# 410_H_BRIDGE_CORE.net
KiCad netlist of a schematic drawn in Altium Designer
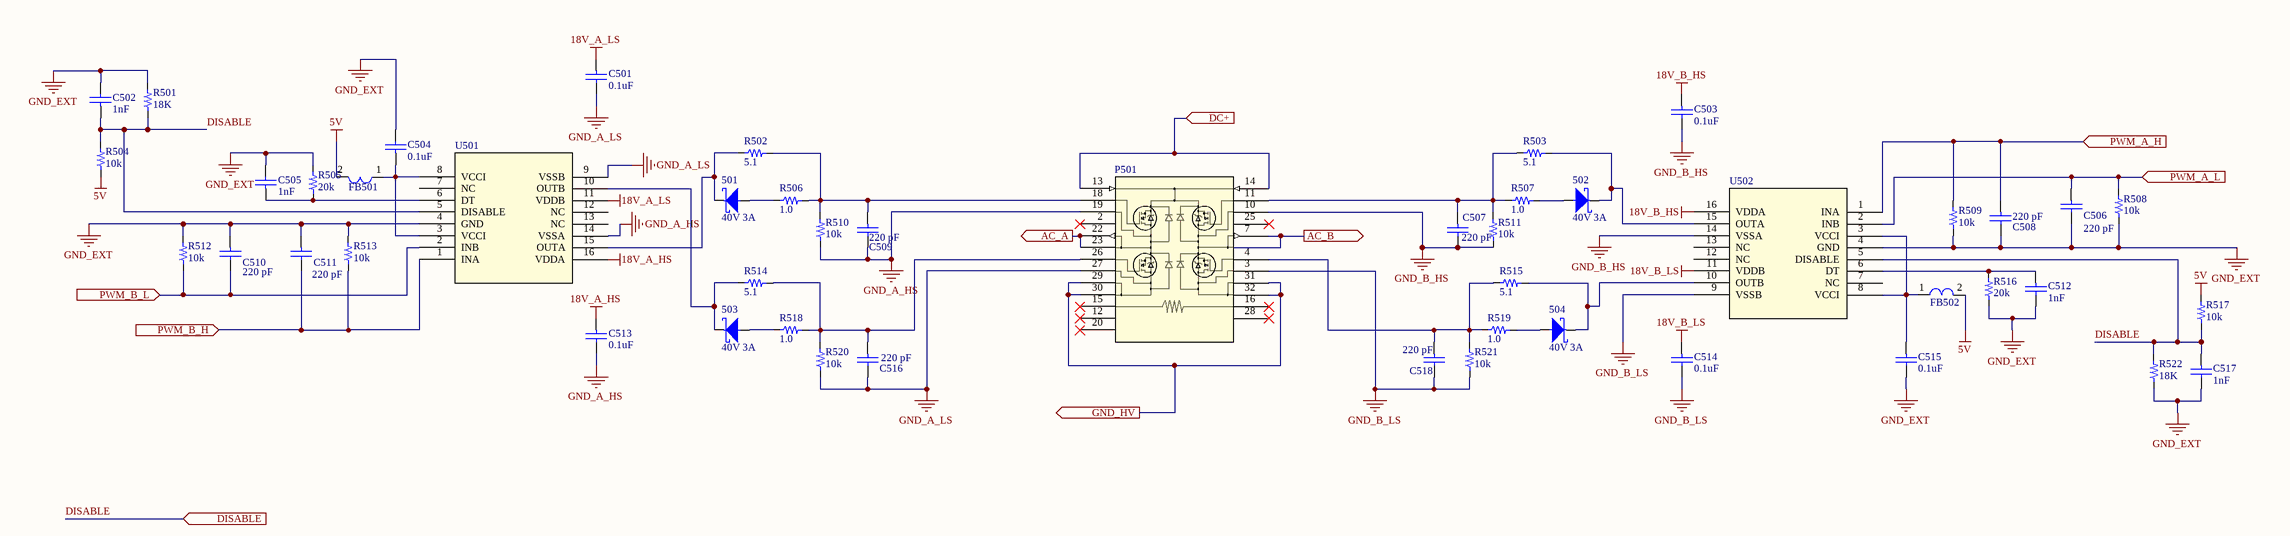
[diagram p0: 410_H_BRIDGE_CORE.SchDoc]

(export (version "E")
  (design (tool "Eeschema 10.0.6"))
  (components
    (comp (ref "501")
      (value "40V 3A")
      (footprint "SMA")
      (description "40V Independent 3A 550mV@3A SMA Schottky Diodes ROHS")
      (fields (field (name "MANUFACTURER") "TDSEMIC") (field (name "MANUFACTURER PART NUMBER") "SS34-TD"))
      (libsource (lib "shared_lib_1") (part "D_Schottky_40V_3A_SMA"))
    )
    (comp (ref "502")
      (value "40V 3A")
      (footprint "SMA")
      (description "40V Independent 3A 550mV@3A SMA Schottky Diodes ROHS")
      (fields (field (name "MANUFACTURER") "TDSEMIC") (field (name "MANUFACTURER PART NUMBER") "SS34-TD"))
      (libsource (lib "shared_lib_1") (part "D_Schottky_40V_3A_SMA"))
    )
    (comp (ref "503")
      (value "40V 3A")
      (footprint "SMA")
      (description "40V Independent 3A 550mV@3A SMA Schottky Diodes ROHS")
      (fields (field (name "MANUFACTURER") "TDSEMIC") (field (name "MANUFACTURER PART NUMBER") "SS34-TD"))
      (libsource (lib "shared_lib_1") (part "D_Schottky_40V_3A_SMA"))
    )
    (comp (ref "504")
      (value "40V 3A")
      (footprint "SMA")
      (description "40V Independent 3A 550mV@3A SMA Schottky Diodes ROHS")
      (fields (field (name "MANUFACTURER") "TDSEMIC") (field (name "MANUFACTURER PART NUMBER") "SS34-TD"))
      (libsource (lib "shared_lib_1") (part "D_Schottky_40V_3A_SMA"))
    )
    (comp (ref "C501")
      (value "0.1uF")
      (footprint "0603_cap")
      (description "50V 100nF Y5V -20%~+80% 0603 Multilayer Ceramic Capacitors MLCC - SMD/SMT ROHS")
      (fields
        (field (name "MANUFACTURER") "Walsin Tech Corp")
        (field (name "MANUFACTURER PART NUMBER") "0603F104Z500CT")
      )
      (libsource (lib "shared_lib_1") (part "Cap_0.1uF_0603_50V"))
    )
    (comp (ref "C502")
      (value "1nF")
      (footprint "0603_cap")
      (description "50V 1nF X7R ±10% 0603 Multilayer Ceramic Capacitors MLCC - SMD/SMT ROHS")
      (fields
        (field (name "MANUFACTURER") "YAGEO")
        (field (name "MANUFACTURER PART NUMBER") "CC0603KRX7R9BB102")
      )
      (libsource (lib "shared_lib_1") (part "Cap_1nF_0603_50V"))
    )
    (comp (ref "C503")
      (value "0.1uF")
      (footprint "0603_cap")
      (description "CAP CER 100nF 50V Y5V 0603")
      (fields
        (field (name "MANUFACTURER") "FOJAN")
        (field (name "MANUFACTURER PART NUMBER") "FCC0603F104Z500CT")
      )
      (libsource (lib "shared_lib_1") (part "Cap_0.1uF_0603_50V"))
    )
    (comp (ref "C504")
      (value "0.1uF")
      (footprint "0603_cap")
      (description "50V 100nF Y5V -20%~+80% 0603 Multilayer Ceramic Capacitors MLCC - SMD/SMT ROHS")
      (fields
        (field (name "MANUFACTURER") "Walsin Tech Corp")
        (field (name "MANUFACTURER PART NUMBER") "0603F104Z500CT")
      )
      (libsource (lib "shared_lib_1") (part "Cap_0.1uF_0603_50V"))
    )
    (comp (ref "C505")
      (value "1nF")
      (footprint "0603_cap")
      (description "50V 1nF X7R ±10% 0603 Multilayer Ceramic Capacitors MLCC - SMD/SMT ROHS")
      (fields
        (field (name "MANUFACTURER") "YAGEO")
        (field (name "MANUFACTURER PART NUMBER") "CC0603KRX7R9BB102")
      )
      (libsource (lib "shared_lib_1") (part "Cap_1nF_0603_50V"))
    )
    (comp (ref "C506")
      (value "220 pF")
      (footprint "0603_cap")
      (description "CAP CER 220pF 50V X7R 0603")
      (fields
        (field (name "MANUFACTURER") "Samsung Electro-Mechanics")
        (field (name "MANUFACTURER PART NUMBER") "CL10B221KB8NNNC")
      )
      (libsource (lib "shared_lib_1") (part "CAP CER_220PF_50V_X7R_0603"))
    )
    (comp (ref "C507")
      (value "220 pF")
      (footprint "0603_cap")
      (description "CAP CER 220pF 50V X7R 0603")
      (fields
        (field (name "MANUFACTURER") "Samsung Electro-Mechanics")
        (field (name "MANUFACTURER PART NUMBER") "CL10B221KB8NNNC")
      )
      (libsource (lib "shared_lib_1") (part "CAP CER_220PF_50V_X7R_0603"))
    )
    (comp (ref "C508")
      (value "220 pF")
      (footprint "0603_cap")
      (description "CAP CER 220pF 50V X7R 0603")
      (fields
        (field (name "MANUFACTURER") "Samsung Electro-Mechanics")
        (field (name "MANUFACTURER PART NUMBER") "CL10B221KB8NNNC")
      )
      (libsource (lib "shared_lib_1") (part "CAP CER_220PF_50V_X7R_0603"))
    )
    (comp (ref "C509")
      (value "220 pF")
      (footprint "0603_cap")
      (description "CAP CER 220pF 50V X7R 0603")
      (fields
        (field (name "MANUFACTURER") "Samsung Electro-Mechanics")
        (field (name "MANUFACTURER PART NUMBER") "CL10B221KB8NNNC")
      )
      (libsource (lib "shared_lib_1") (part "CAP CER_220PF_50V_X7R_0603"))
    )
    (comp (ref "C510")
      (value "220 pF")
      (footprint "0603_cap")
      (description "CAP CER 220pF 50V X7R 0603")
      (fields
        (field (name "MANUFACTURER") "Samsung Electro-Mechanics")
        (field (name "MANUFACTURER PART NUMBER") "CL10B221KB8NNNC")
      )
      (libsource (lib "shared_lib_1") (part "CAP CER_220PF_50V_X7R_0603"))
    )
    (comp (ref "C511")
      (value "220 pF")
      (footprint "0603_cap")
      (description "CAP CER 220pF 50V X7R 0603")
      (fields
        (field (name "MANUFACTURER") "Samsung Electro-Mechanics")
        (field (name "MANUFACTURER PART NUMBER") "CL10B221KB8NNNC")
      )
      (libsource (lib "shared_lib_1") (part "CAP CER_220PF_50V_X7R_0603"))
    )
    (comp (ref "C512")
      (value "1nF")
      (footprint "0603_cap")
      (description "50V 1nF X7R ±10% 0603 Multilayer Ceramic Capacitors MLCC - SMD/SMT ROHS")
      (fields
        (field (name "MANUFACTURER") "YAGEO")
        (field (name "MANUFACTURER PART NUMBER") "CC0603KRX7R9BB102")
      )
      (libsource (lib "shared_lib_1") (part "Cap_1nF_0603_50V"))
    )
    (comp (ref "C513")
      (value "0.1uF")
      (footprint "0603_cap")
      (description "50V 100nF Y5V -20%~+80% 0603 Multilayer Ceramic Capacitors MLCC - SMD/SMT ROHS")
      (fields
        (field (name "MANUFACTURER") "Walsin Tech Corp")
        (field (name "MANUFACTURER PART NUMBER") "0603F104Z500CT")
      )
      (libsource (lib "shared_lib_1") (part "Cap_0.1uF_0603_50V"))
    )
    (comp (ref "C514")
      (value "0.1uF")
      (footprint "0603_cap")
      (description "50V 100nF Y5V -20%~+80% 0603 Multilayer Ceramic Capacitors MLCC - SMD/SMT ROHS")
      (fields
        (field (name "MANUFACTURER") "Walsin Tech Corp")
        (field (name "MANUFACTURER PART NUMBER") "0603F104Z500CT")
      )
      (libsource (lib "shared_lib_1") (part "Cap_0.1uF_0603_50V"))
    )
    (comp (ref "C515")
      (value "0.1uF")
      (footprint "0603_cap")
      (description "50V 100nF Y5V -20%~+80% 0603 Multilayer Ceramic Capacitors MLCC - SMD/SMT ROHS")
      (fields
        (field (name "MANUFACTURER") "Walsin Tech Corp")
        (field (name "MANUFACTURER PART NUMBER") "0603F104Z500CT")
      )
      (libsource (lib "shared_lib_1") (part "Cap_0.1uF_0603_50V"))
    )
    (comp (ref "C516")
      (value "220 pF")
      (footprint "0603_cap")
      (description "CAP CER 220pF 50V X7R 0603")
      (fields
        (field (name "MANUFACTURER") "Samsung Electro-Mechanics")
        (field (name "MANUFACTURER PART NUMBER") "CL10B221KB8NNNC")
      )
      (libsource (lib "shared_lib_1") (part "CAP CER_220PF_50V_X7R_0603"))
    )
    (comp (ref "C517")
      (value "1nF")
      (footprint "0603_cap")
      (description "50V 1nF X7R ±10% 0603 Multilayer Ceramic Capacitors MLCC - SMD/SMT ROHS")
      (fields
        (field (name "MANUFACTURER") "YAGEO")
        (field (name "MANUFACTURER PART NUMBER") "CC0603KRX7R9BB102")
      )
      (libsource (lib "shared_lib_1") (part "Cap_1nF_0603_50V"))
    )
    (comp (ref "C518")
      (value "220 pF")
      (footprint "0603_cap")
      (description "CAP CER 220pF 50V X7R 0603")
      (fields
        (field (name "MANUFACTURER") "Samsung Electro-Mechanics")
        (field (name "MANUFACTURER PART NUMBER") "CL10B221KB8NNNC")
      )
      (libsource (lib "shared_lib_1") (part "CAP CER_220PF_50V_X7R_0603"))
    )
    (comp (ref "FB501")
      (value "~")
      (footprint "MH1608")
      (description "FERRITE BEAD 600 OHM 0603 4LN")
      (fields
        (field (name "MANUFACTURER") "Bourns Inc.")
        (field (name "MANUFACTURER PART NUMBER") "MH1608-601Y")
      )
      (libsource (lib "shared_lib_1") (part "FERRITE_BEAD_600_OHM"))
    )
    (comp (ref "FB502")
      (value "~")
      (footprint "MH1608")
      (description "FERRITE BEAD 600 OHM 0603 4LN")
      (fields
        (field (name "MANUFACTURER") "Bourns Inc.")
        (field (name "MANUFACTURER PART NUMBER") "MH1608-601Y")
      )
      (libsource (lib "shared_lib_1") (part "FERRITE_BEAD_600_OHM"))
    )
    (comp (ref "P501")
      (value "~")
      (footprint "SP3F_MCH")
      (description "MOSFET - Arreglos 1200V (1.2kV) 173H (Tc) 745W (Tc) Montaje de chasis SP3F")
      (fields
        (field (name "MANUFACTURER") "Microchip Technology")
        (field (name "MANUFACTURER PART NUMBER") "MSCSM120HM16CT3AG")
      )
      (libsource (lib "shared_lib_1") (part "MOSFET_4N-CH"))
    )
    (comp (ref "R501")
      (value "18K")
      (footprint "0603_res")
      (fields
        (field (name "MANUFACTURER") "YAGEO")
        (field (name "MANUFACTURER PART NUMBER") "RC0603JR-0718KL")
      )
      (libsource (lib "shared_lib_1") (part "RES_18K_OHM _0603"))
    )
    (comp (ref "R502")
      (value "5.1")
      (footprint "0603_res")
      (fields
        (field (name "MANUFACTURER") "VISHAY")
        (field (name "MANUFACTURER PART NUMBER") "CRCW06035R10FKEA")
      )
      (libsource (lib "shared_lib_1") (part "RES_SMD_5.1_OHM_0603"))
    )
    (comp (ref "R503")
      (value "5.1")
      (footprint "0603_res")
      (fields
        (field (name "MANUFACTURER") "VISHAY")
        (field (name "MANUFACTURER PART NUMBER") "CRCW06035R10FKEA")
      )
      (libsource (lib "shared_lib_1") (part "RES_SMD_5.1_OHM_0603"))
    )
    (comp (ref "R504")
      (value "10k")
      (footprint "0603_res")
      (description "RES SMD 10k OHM 5% 1/10W 0603")
      (fields (field (name "MANUFACTURER") "FOJAN") (field (name "MANUFACTURER PART NUMBER") "FRC0603J103TS"))
      (libsource (lib "shared_lib_1") (part "Res_10k_0603_1/10W"))
    )
    (comp (ref "R505")
      (value "20k")
      (footprint "0603_res")
      (description "RES 20kΩ ±1% 100mW 0603")
      (fields
        (field (name "MANUFACTURER") "FOJAN")
        (field (name "MANUFACTURER PART NUMBER") "FRC0603F2002TS")
      )
      (libsource (lib "shared_lib_1") (part "RES_20K_OHM_0603"))
    )
    (comp (ref "R506")
      (value "1.0")
      (footprint "0603_res")
      (fields
        (field (name "MANUFACTURER") "YAGEO")
        (field (name "MANUFACTURER PART NUMBER") "RC0603FR-071RL")
      )
      (libsource (lib "shared_lib_1") (part "RES_1_OHM_0603"))
    )
    (comp (ref "R507")
      (value "1.0")
      (footprint "0603_res")
      (fields
        (field (name "MANUFACTURER") "YAGEO")
        (field (name "MANUFACTURER PART NUMBER") "RC0603FR-071RL")
      )
      (libsource (lib "shared_lib_1") (part "RES_1_OHM_0603"))
    )
    (comp (ref "R508")
      (value "10k")
      (footprint "0603_res")
      (description "RES SMD 10k OHM 5% 1/10W 0603")
      (fields (field (name "MANUFACTURER") "FOJAN") (field (name "MANUFACTURER PART NUMBER") "FRC0603J103TS"))
      (libsource (lib "shared_lib_1") (part "Res_10k_0603_1/10W"))
    )
    (comp (ref "R509")
      (value "10k")
      (footprint "0603_res")
      (description "RES SMD 10k OHM 5% 1/10W 0603")
      (fields (field (name "MANUFACTURER") "FOJAN") (field (name "MANUFACTURER PART NUMBER") "FRC0603J103TS"))
      (libsource (lib "shared_lib_1") (part "Res_10k_0603_1/10W"))
    )
    (comp (ref "R510")
      (value "10k")
      (footprint "0603_res")
      (description "RES SMD 10k OHM 5% 1/10W 0603")
      (fields (field (name "MANUFACTURER") "FOJAN") (field (name "MANUFACTURER PART NUMBER") "FRC0603J103TS"))
      (libsource (lib "shared_lib_1") (part "Res_10k_0603_1/10W"))
    )
    (comp (ref "R511")
      (value "10k")
      (footprint "0603_res")
      (description "RES SMD 10k OHM 5% 1/10W 0603")
      (fields (field (name "MANUFACTURER") "FOJAN") (field (name "MANUFACTURER PART NUMBER") "FRC0603J103TS"))
      (libsource (lib "shared_lib_1") (part "Res_10k_0603_1/10W"))
    )
    (comp (ref "R512")
      (value "10k")
      (footprint "0603_res")
      (description "RES SMD 10k OHM 5% 1/10W 0603")
      (fields (field (name "MANUFACTURER") "FOJAN") (field (name "MANUFACTURER PART NUMBER") "FRC0603J103TS"))
      (libsource (lib "shared_lib_1") (part "Res_10k_0603_1/10W"))
    )
    (comp (ref "R513")
      (value "10k")
      (footprint "0603_res")
      (description "RES SMD 10k OHM 5% 1/10W 0603")
      (fields (field (name "MANUFACTURER") "FOJAN") (field (name "MANUFACTURER PART NUMBER") "FRC0603J103TS"))
      (libsource (lib "shared_lib_1") (part "Res_10k_0603_1/10W"))
    )
    (comp (ref "R514")
      (value "5.1")
      (footprint "0603_res")
      (fields
        (field (name "MANUFACTURER") "VISHAY")
        (field (name "MANUFACTURER PART NUMBER") "CRCW06035R10FKEA")
      )
      (libsource (lib "shared_lib_1") (part "RES_SMD_5.1_OHM_0603"))
    )
    (comp (ref "R515")
      (value "5.1")
      (footprint "0603_res")
      (fields
        (field (name "MANUFACTURER") "VISHAY")
        (field (name "MANUFACTURER PART NUMBER") "CRCW06035R10FKEA")
      )
      (libsource (lib "shared_lib_1") (part "RES_SMD_5.1_OHM_0603"))
    )
    (comp (ref "R516")
      (value "20k")
      (footprint "0603_res")
      (description "RES 20kΩ ±1% 100mW 0603")
      (fields
        (field (name "MANUFACTURER") "FOJAN")
        (field (name "MANUFACTURER PART NUMBER") "FRC0603F2002TS")
      )
      (libsource (lib "shared_lib_1") (part "RES_20K_OHM_0603"))
    )
    (comp (ref "R517")
      (value "10k")
      (footprint "0603_res")
      (description "RES SMD 10k OHM 5% 1/10W 0603")
      (fields (field (name "MANUFACTURER") "FOJAN") (field (name "MANUFACTURER PART NUMBER") "FRC0603J103TS"))
      (libsource (lib "shared_lib_1") (part "Res_10k_0603_1/10W"))
    )
    (comp (ref "R518")
      (value "1.0")
      (footprint "0603_res")
      (fields
        (field (name "MANUFACTURER") "YAGEO")
        (field (name "MANUFACTURER PART NUMBER") "RC0603FR-071RL")
      )
      (libsource (lib "shared_lib_1") (part "RES_1_OHM_0603"))
    )
    (comp (ref "R519")
      (value "1.0")
      (footprint "0603_res")
      (fields
        (field (name "MANUFACTURER") "YAGEO")
        (field (name "MANUFACTURER PART NUMBER") "RC0603FR-071RL")
      )
      (libsource (lib "shared_lib_1") (part "RES_1_OHM_0603"))
    )
    (comp (ref "R520")
      (value "10k")
      (footprint "0603_res")
      (description "RES SMD 10k OHM 5% 1/10W 0603")
      (fields (field (name "MANUFACTURER") "FOJAN") (field (name "MANUFACTURER PART NUMBER") "FRC0603J103TS"))
      (libsource (lib "shared_lib_1") (part "Res_10k_0603_1/10W"))
    )
    (comp (ref "R521")
      (value "10k")
      (footprint "0603_res")
      (description "RES SMD 10k OHM 5% 1/10W 0603")
      (fields (field (name "MANUFACTURER") "FOJAN") (field (name "MANUFACTURER PART NUMBER") "FRC0603J103TS"))
      (libsource (lib "shared_lib_1") (part "Res_10k_0603_1/10W"))
    )
    (comp (ref "R522")
      (value "18K")
      (footprint "0603_res")
      (fields
        (field (name "MANUFACTURER") "YAGEO")
        (field (name "MANUFACTURER PART NUMBER") "RC0603JR-0718KL")
      )
      (libsource (lib "shared_lib_1") (part "RES_18K_OHM _0603"))
    )
    (comp (ref "U501")
      (value "~")
      (footprint "UCC21540DW")
      (description "4A, 6A Controladores de compuerta Acoplamiento capacitivo 5700Vrms 2 canal 16-SOIC")
      (fields
        (field (name "MANUFACTURER") "Texas Instruments")
        (field (name "MANUFACTURER PART NUMBER") "UCC21540DW")
      )
      (libsource (lib "") (part "DGTL ISO 5.7KV 2CH GT DVR 16SOIC_1"))
    )
    (comp (ref "U502")
      (value "~")
      (footprint "UCC21540DW")
      (description "4A, 6A Controladores de compuerta Acoplamiento capacitivo 5700Vrms 2 canal 16-SOIC")
      (fields
        (field (name "MANUFACTURER") "Texas Instruments")
        (field (name "MANUFACTURER PART NUMBER") "UCC21540DW")
      )
      (libsource (lib "shared_lib_1") (part "DGTL ISO 5.7KV 2CH GT DVR 16SOIC"))
    )
  )
  (nets
    (net (code "1") (name "/AC_A") (class "Default")
      (node (ref "P501") (pin "22") (pinfunction "22_22") (pintype "output"))
      (node (ref "P501") (pin "23") (pinfunction "23_23") (pintype "passive"))
    )
    (net (code "2") (name "/AC_B") (class "Default")
      (node (ref "P501") (pin "7") (pinfunction "7_7") (pintype "output"))
    )
    (net (code "3") (name "/DC+") (class "Default")
      (node (ref "P501") (pin "13") (pinfunction "13_13") (pintype "input"))
      (node (ref "P501") (pin "14") (pinfunction "14_14") (pintype "input"))
    )
    (net (code "4") (name "/DISABLE") (class "Default")
      (node (ref "C502") (pin "1") (pinfunction "1_1") (pintype "passive"))
      (node (ref "C517") (pin "1") (pinfunction "1_1") (pintype "passive"))
      (node (ref "R501") (pin "1") (pinfunction "1_1") (pintype "passive"))
      (node (ref "R504") (pin "2") (pinfunction "2_2") (pintype "passive"))
      (node (ref "R517") (pin "1") (pinfunction "1_1") (pintype "passive"))
      (node (ref "R522") (pin "2") (pinfunction "2_2") (pintype "passive"))
      (node (ref "U501") (pin "5") (pinfunction "DISABLE_5") (pintype "passive"))
      (node (ref "U502") (pin "5") (pinfunction "DISABLE_5") (pintype "passive"))
    )
    (net (code "5") (name "/GND_HV") (class "Default")
      (node (ref "P501") (pin "29") (pinfunction "29_29") (pintype "passive"))
      (node (ref "P501") (pin "30") (pinfunction "30_30") (pintype "passive"))
      (node (ref "P501") (pin "31") (pinfunction "31_31") (pintype "passive"))
      (node (ref "P501") (pin "32") (pinfunction "32_32") (pintype "passive"))
    )
    (net (code "6") (name "/PWM_A_H") (class "Default")
      (node (ref "C508") (pin "1") (pinfunction "1_1") (pintype "passive"))
      (node (ref "R509") (pin "2") (pinfunction "2_2") (pintype "passive"))
      (node (ref "U502") (pin "1") (pinfunction "INA_1") (pintype "passive"))
    )
    (net (code "7") (name "/PWM_A_L") (class "Default")
      (node (ref "C506") (pin "1") (pinfunction "1_1") (pintype "passive"))
      (node (ref "R508") (pin "2") (pinfunction "2_2") (pintype "passive"))
      (node (ref "U502") (pin "2") (pinfunction "INB_2") (pintype "passive"))
    )
    (net (code "8") (name "/PWM_B_H") (class "Default")
      (node (ref "C511") (pin "2") (pinfunction "2_2") (pintype "passive"))
      (node (ref "R513") (pin "1") (pinfunction "1_1") (pintype "passive"))
      (node (ref "U501") (pin "1") (pinfunction "INA_1") (pintype "passive"))
    )
    (net (code "9") (name "/PWM_B_L") (class "Default")
      (node (ref "C510") (pin "2") (pinfunction "2_2") (pintype "passive"))
      (node (ref "R512") (pin "1") (pinfunction "1_1") (pintype "passive"))
      (node (ref "U501") (pin "2") (pinfunction "INB_2") (pintype "passive"))
    )
    (net (code "10") (name "5V") (class "Default")
      (node (ref "FB501") (pin "2") (pinfunction "2_2") (pintype "passive"))
      (node (ref "FB502") (pin "2") (pinfunction "2_2") (pintype "passive"))
      (node (ref "R504") (pin "1") (pinfunction "1_1") (pintype "passive"))
      (node (ref "R517") (pin "2") (pinfunction "2_2") (pintype "passive"))
    )
    (net (code "11") (name "18V_A_HS") (class "Default")
      (node (ref "C513") (pin "1") (pinfunction "1_1") (pintype "passive"))
      (node (ref "U501") (pin "16") (pinfunction "VDDA_16") (pintype "passive"))
    )
    (net (code "12") (name "18V_A_LS") (class "Default")
      (node (ref "C501") (pin "1") (pinfunction "1_1") (pintype "passive"))
      (node (ref "U501") (pin "11") (pinfunction "VDDB_11") (pintype "passive"))
    )
    (net (code "13") (name "18V_B_HS") (class "Default")
      (node (ref "C503") (pin "1") (pinfunction "1_1") (pintype "passive"))
      (node (ref "U502") (pin "16") (pinfunction "VDDA_16") (pintype "passive"))
    )
    (net (code "14") (name "18V_B_LS") (class "Default")
      (node (ref "C514") (pin "1") (pinfunction "1_1") (pintype "passive"))
      (node (ref "U502") (pin "11") (pinfunction "VDDB_11") (pintype "passive"))
    )
    (net (code "15") (name "GND_A_HS") (class "Default")
      (node (ref "C509") (pin "2") (pinfunction "2_2") (pintype "passive"))
      (node (ref "C513") (pin "2") (pinfunction "2_2") (pintype "passive"))
      (node (ref "P501") (pin "19") (pinfunction "19_19") (pintype "passive"))
      (node (ref "R510") (pin "1") (pinfunction "1_1") (pintype "passive"))
      (node (ref "U501") (pin "14") (pinfunction "VSSA_14") (pintype "power_in"))
    )
    (net (code "16") (name "GND_A_LS") (class "Default")
      (node (ref "C501") (pin "2") (pinfunction "2_2") (pintype "passive"))
      (node (ref "C516") (pin "2") (pinfunction "2_2") (pintype "passive"))
      (node (ref "P501") (pin "27") (pinfunction "27_27") (pintype "passive"))
      (node (ref "R520") (pin "1") (pinfunction "1_1") (pintype "passive"))
      (node (ref "U501") (pin "9") (pinfunction "VSSB_9") (pintype "power_in"))
    )
    (net (code "17") (name "GND_B_HS") (class "Default")
      (node (ref "C503") (pin "2") (pinfunction "2_2") (pintype "passive"))
      (node (ref "C507") (pin "2") (pinfunction "2_2") (pintype "passive"))
      (node (ref "P501") (pin "10") (pinfunction "10_10") (pintype "passive"))
      (node (ref "R511") (pin "1") (pinfunction "1_1") (pintype "passive"))
      (node (ref "U502") (pin "14") (pinfunction "VSSA_14") (pintype "power_in"))
    )
    (net (code "18") (name "GND_B_LS") (class "Default")
      (node (ref "C514") (pin "2") (pinfunction "2_2") (pintype "passive"))
      (node (ref "C518") (pin "2") (pinfunction "2_2") (pintype "passive"))
      (node (ref "P501") (pin "3") (pinfunction "3_3") (pintype "passive"))
      (node (ref "R521") (pin "1") (pinfunction "1_1") (pintype "passive"))
      (node (ref "U502") (pin "9") (pinfunction "VSSB_9") (pintype "power_in"))
    )
    (net (code "19") (name "GND_EXT") (class "Default")
      (node (ref "C502") (pin "2") (pinfunction "2_2") (pintype "passive"))
      (node (ref "C504") (pin "2") (pinfunction "2_2") (pintype "passive"))
      (node (ref "C505") (pin "2") (pinfunction "2_2") (pintype "passive"))
      (node (ref "C506") (pin "2") (pinfunction "2_2") (pintype "passive"))
      (node (ref "C508") (pin "2") (pinfunction "2_2") (pintype "passive"))
      (node (ref "C510") (pin "1") (pinfunction "1_1") (pintype "passive"))
      (node (ref "C511") (pin "1") (pinfunction "1_1") (pintype "passive"))
      (node (ref "C512") (pin "2") (pinfunction "2_2") (pintype "passive"))
      (node (ref "C515") (pin "2") (pinfunction "2_2") (pintype "passive"))
      (node (ref "C517") (pin "2") (pinfunction "2_2") (pintype "passive"))
      (node (ref "R501") (pin "2") (pinfunction "2_2") (pintype "passive"))
      (node (ref "R505") (pin "2") (pinfunction "2_2") (pintype "passive"))
      (node (ref "R508") (pin "1") (pinfunction "1_1") (pintype "passive"))
      (node (ref "R509") (pin "1") (pinfunction "1_1") (pintype "passive"))
      (node (ref "R512") (pin "2") (pinfunction "2_2") (pintype "passive"))
      (node (ref "R513") (pin "2") (pinfunction "2_2") (pintype "passive"))
      (node (ref "R516") (pin "1") (pinfunction "1_1") (pintype "passive"))
      (node (ref "R522") (pin "1") (pinfunction "1_1") (pintype "passive"))
      (node (ref "U501") (pin "4") (pinfunction "GND_4") (pintype "passive"))
      (node (ref "U502") (pin "4") (pinfunction "GND_4") (pintype "passive"))
    )
    (net (code "20") (name "Net-(501-Pad2)") (class "Default")
      (node (ref "501") (pin "2") (pinfunction "2_2") (pintype "passive"))
      (node (ref "R506") (pin "1") (pinfunction "1_1") (pintype "passive"))
    )
    (net (code "21") (name "Net-(502-Pad2)") (class "Default")
      (node (ref "502") (pin "2") (pinfunction "2_2") (pintype "passive"))
      (node (ref "R507") (pin "2") (pinfunction "2_2") (pintype "passive"))
    )
    (net (code "22") (name "Net-(503-Pad2)") (class "Default")
      (node (ref "503") (pin "2") (pinfunction "2_2") (pintype "passive"))
      (node (ref "R518") (pin "1") (pinfunction "1_1") (pintype "passive"))
    )
    (net (code "23") (name "Net-(504-Pad2)") (class "Default")
      (node (ref "504") (pin "2") (pinfunction "2_2") (pintype "passive"))
      (node (ref "R519") (pin "2") (pinfunction "2_2") (pintype "passive"))
    )
    (net (code "24") (name "Net-(C504-Pad1)") (class "Default")
      (node (ref "C504") (pin "1") (pinfunction "1_1") (pintype "passive"))
      (node (ref "FB501") (pin "1") (pinfunction "1_1") (pintype "passive"))
      (node (ref "U501") (pin "3") (pinfunction "VCCI_3") (pintype "power_in"))
      (node (ref "U501") (pin "8") (pinfunction "VCCI_8") (pintype "power_in"))
    )
    (net (code "25") (name "Net-(C507-Pad1)") (class "Default")
      (node (ref "C507") (pin "1") (pinfunction "1_1") (pintype "passive"))
      (node (ref "P501") (pin "11") (pinfunction "11_11") (pintype "passive"))
      (node (ref "R503") (pin "1") (pinfunction "1_1") (pintype "passive"))
      (node (ref "R507") (pin "1") (pinfunction "1_1") (pintype "passive"))
      (node (ref "R511") (pin "2") (pinfunction "2_2") (pintype "passive"))
    )
    (net (code "26") (name "Net-(C509-Pad1)") (class "Default")
      (node (ref "C509") (pin "1") (pinfunction "1_1") (pintype "passive"))
      (node (ref "P501") (pin "18") (pinfunction "18_18") (pintype "passive"))
      (node (ref "R502") (pin "2") (pinfunction "2_2") (pintype "passive"))
      (node (ref "R506") (pin "2") (pinfunction "2_2") (pintype "passive"))
      (node (ref "R510") (pin "2") (pinfunction "2_2") (pintype "passive"))
    )
    (net (code "27") (name "Net-(C515-Pad1)") (class "Default")
      (node (ref "C515") (pin "1") (pinfunction "1_1") (pintype "passive"))
      (node (ref "FB502") (pin "1") (pinfunction "1_1") (pintype "passive"))
      (node (ref "U502") (pin "3") (pinfunction "VCCI_3") (pintype "power_in"))
      (node (ref "U502") (pin "8") (pinfunction "VCCI_8") (pintype "power_in"))
    )
    (net (code "28") (name "Net-(C516-Pad1)") (class "Default")
      (node (ref "C516") (pin "1") (pinfunction "1_1") (pintype "passive"))
      (node (ref "P501") (pin "26") (pinfunction "26_26") (pintype "passive"))
      (node (ref "R514") (pin "2") (pinfunction "2_2") (pintype "passive"))
      (node (ref "R518") (pin "2") (pinfunction "2_2") (pintype "passive"))
      (node (ref "R520") (pin "2") (pinfunction "2_2") (pintype "passive"))
    )
    (net (code "29") (name "Net-(C518-Pad1)") (class "Default")
      (node (ref "C518") (pin "1") (pinfunction "1_1") (pintype "passive"))
      (node (ref "P501") (pin "4") (pinfunction "4_4") (pintype "passive"))
      (node (ref "R515") (pin "1") (pinfunction "1_1") (pintype "passive"))
      (node (ref "R519") (pin "1") (pinfunction "1_1") (pintype "passive"))
      (node (ref "R521") (pin "2") (pinfunction "2_2") (pintype "passive"))
    )
    (net (code "30") (name "Net-(U501-DT)") (class "Default")
      (node (ref "C505") (pin "1") (pinfunction "1_1") (pintype "passive"))
      (node (ref "R505") (pin "1") (pinfunction "1_1") (pintype "passive"))
      (node (ref "U501") (pin "6") (pinfunction "DT_6") (pintype "passive"))
    )
    (net (code "31") (name "Net-(U501-OUTA)") (class "Default")
      (node (ref "501") (pin "1") (pinfunction "1_1") (pintype "passive"))
      (node (ref "R502") (pin "1") (pinfunction "1_1") (pintype "passive"))
      (node (ref "U501") (pin "15") (pinfunction "OUTA_15") (pintype "passive"))
    )
    (net (code "32") (name "Net-(U501-OUTB)") (class "Default")
      (node (ref "503") (pin "1") (pinfunction "1_1") (pintype "passive"))
      (node (ref "R514") (pin "1") (pinfunction "1_1") (pintype "passive"))
      (node (ref "U501") (pin "10") (pinfunction "OUTB_10") (pintype "passive"))
    )
    (net (code "33") (name "Net-(U502-DT)") (class "Default")
      (node (ref "C512") (pin "1") (pinfunction "1_1") (pintype "passive"))
      (node (ref "R516") (pin "2") (pinfunction "2_2") (pintype "passive"))
      (node (ref "U502") (pin "6") (pinfunction "DT_6") (pintype "passive"))
    )
    (net (code "34") (name "Net-(U502-OUTA)") (class "Default")
      (node (ref "502") (pin "1") (pinfunction "1_1") (pintype "passive"))
      (node (ref "R503") (pin "2") (pinfunction "2_2") (pintype "passive"))
      (node (ref "U502") (pin "15") (pinfunction "OUTA_15") (pintype "passive"))
    )
    (net (code "35") (name "Net-(U502-OUTB)") (class "Default")
      (node (ref "504") (pin "1") (pinfunction "1_1") (pintype "passive"))
      (node (ref "R515") (pin "2") (pinfunction "2_2") (pintype "passive"))
      (node (ref "U502") (pin "10") (pinfunction "OUTB_10") (pintype "passive"))
    )
    (net (code "36") (name "unconnected-(P501-Pad2)") (class "Default")
      (node (ref "P501") (pin "2") (pinfunction "2_2") (pintype "passive+no_connect"))
    )
    (net (code "37") (name "unconnected-(P501-Pad12)") (class "Default")
      (node (ref "P501") (pin "12") (pinfunction "12_12") (pintype "passive+no_connect"))
    )
    (net (code "38") (name "unconnected-(P501-Pad15)") (class "Default")
      (node (ref "P501") (pin "15") (pinfunction "15_15") (pintype "passive+no_connect"))
    )
    (net (code "39") (name "unconnected-(P501-Pad16)") (class "Default")
      (node (ref "P501") (pin "16") (pinfunction "16_16") (pintype "passive+no_connect"))
    )
    (net (code "40") (name "unconnected-(P501-Pad20)") (class "Default")
      (node (ref "P501") (pin "20") (pinfunction "20_20") (pintype "passive+no_connect"))
    )
    (net (code "41") (name "unconnected-(P501-Pad25)") (class "Default")
      (node (ref "P501") (pin "25") (pinfunction "25_25") (pintype "passive+no_connect"))
    )
    (net (code "42") (name "unconnected-(P501-Pad28)") (class "Default")
      (node (ref "P501") (pin "28") (pinfunction "28_28") (pintype "passive+no_connect"))
    )
    (net (code "43") (name "unconnected-(U501-NC-Pad7)") (class "Default")
      (node (ref "U501") (pin "7") (pinfunction "NC_7") (pintype "passive"))
    )
    (net (code "44") (name "unconnected-(U501-NC-Pad12)") (class "Default")
      (node (ref "U501") (pin "12") (pinfunction "NC_12") (pintype "passive"))
    )
    (net (code "45") (name "unconnected-(U501-NC-Pad13)") (class "Default")
      (node (ref "U501") (pin "13") (pinfunction "NC_13") (pintype "power_in"))
    )
    (net (code "46") (name "unconnected-(U502-NC-Pad7)") (class "Default")
      (node (ref "U502") (pin "7") (pinfunction "NC_7") (pintype "passive"))
    )
    (net (code "47") (name "unconnected-(U502-NC-Pad12)") (class "Default")
      (node (ref "U502") (pin "12") (pinfunction "NC_12") (pintype "passive"))
    )
    (net (code "48") (name "unconnected-(U502-NC-Pad13)") (class "Default")
      (node (ref "U502") (pin "13") (pinfunction "NC_13") (pintype "power_in"))
    )
  )
)
